# Jumbo_Programmer.net
KiCad netlist of a schematic drawn in EAGLE
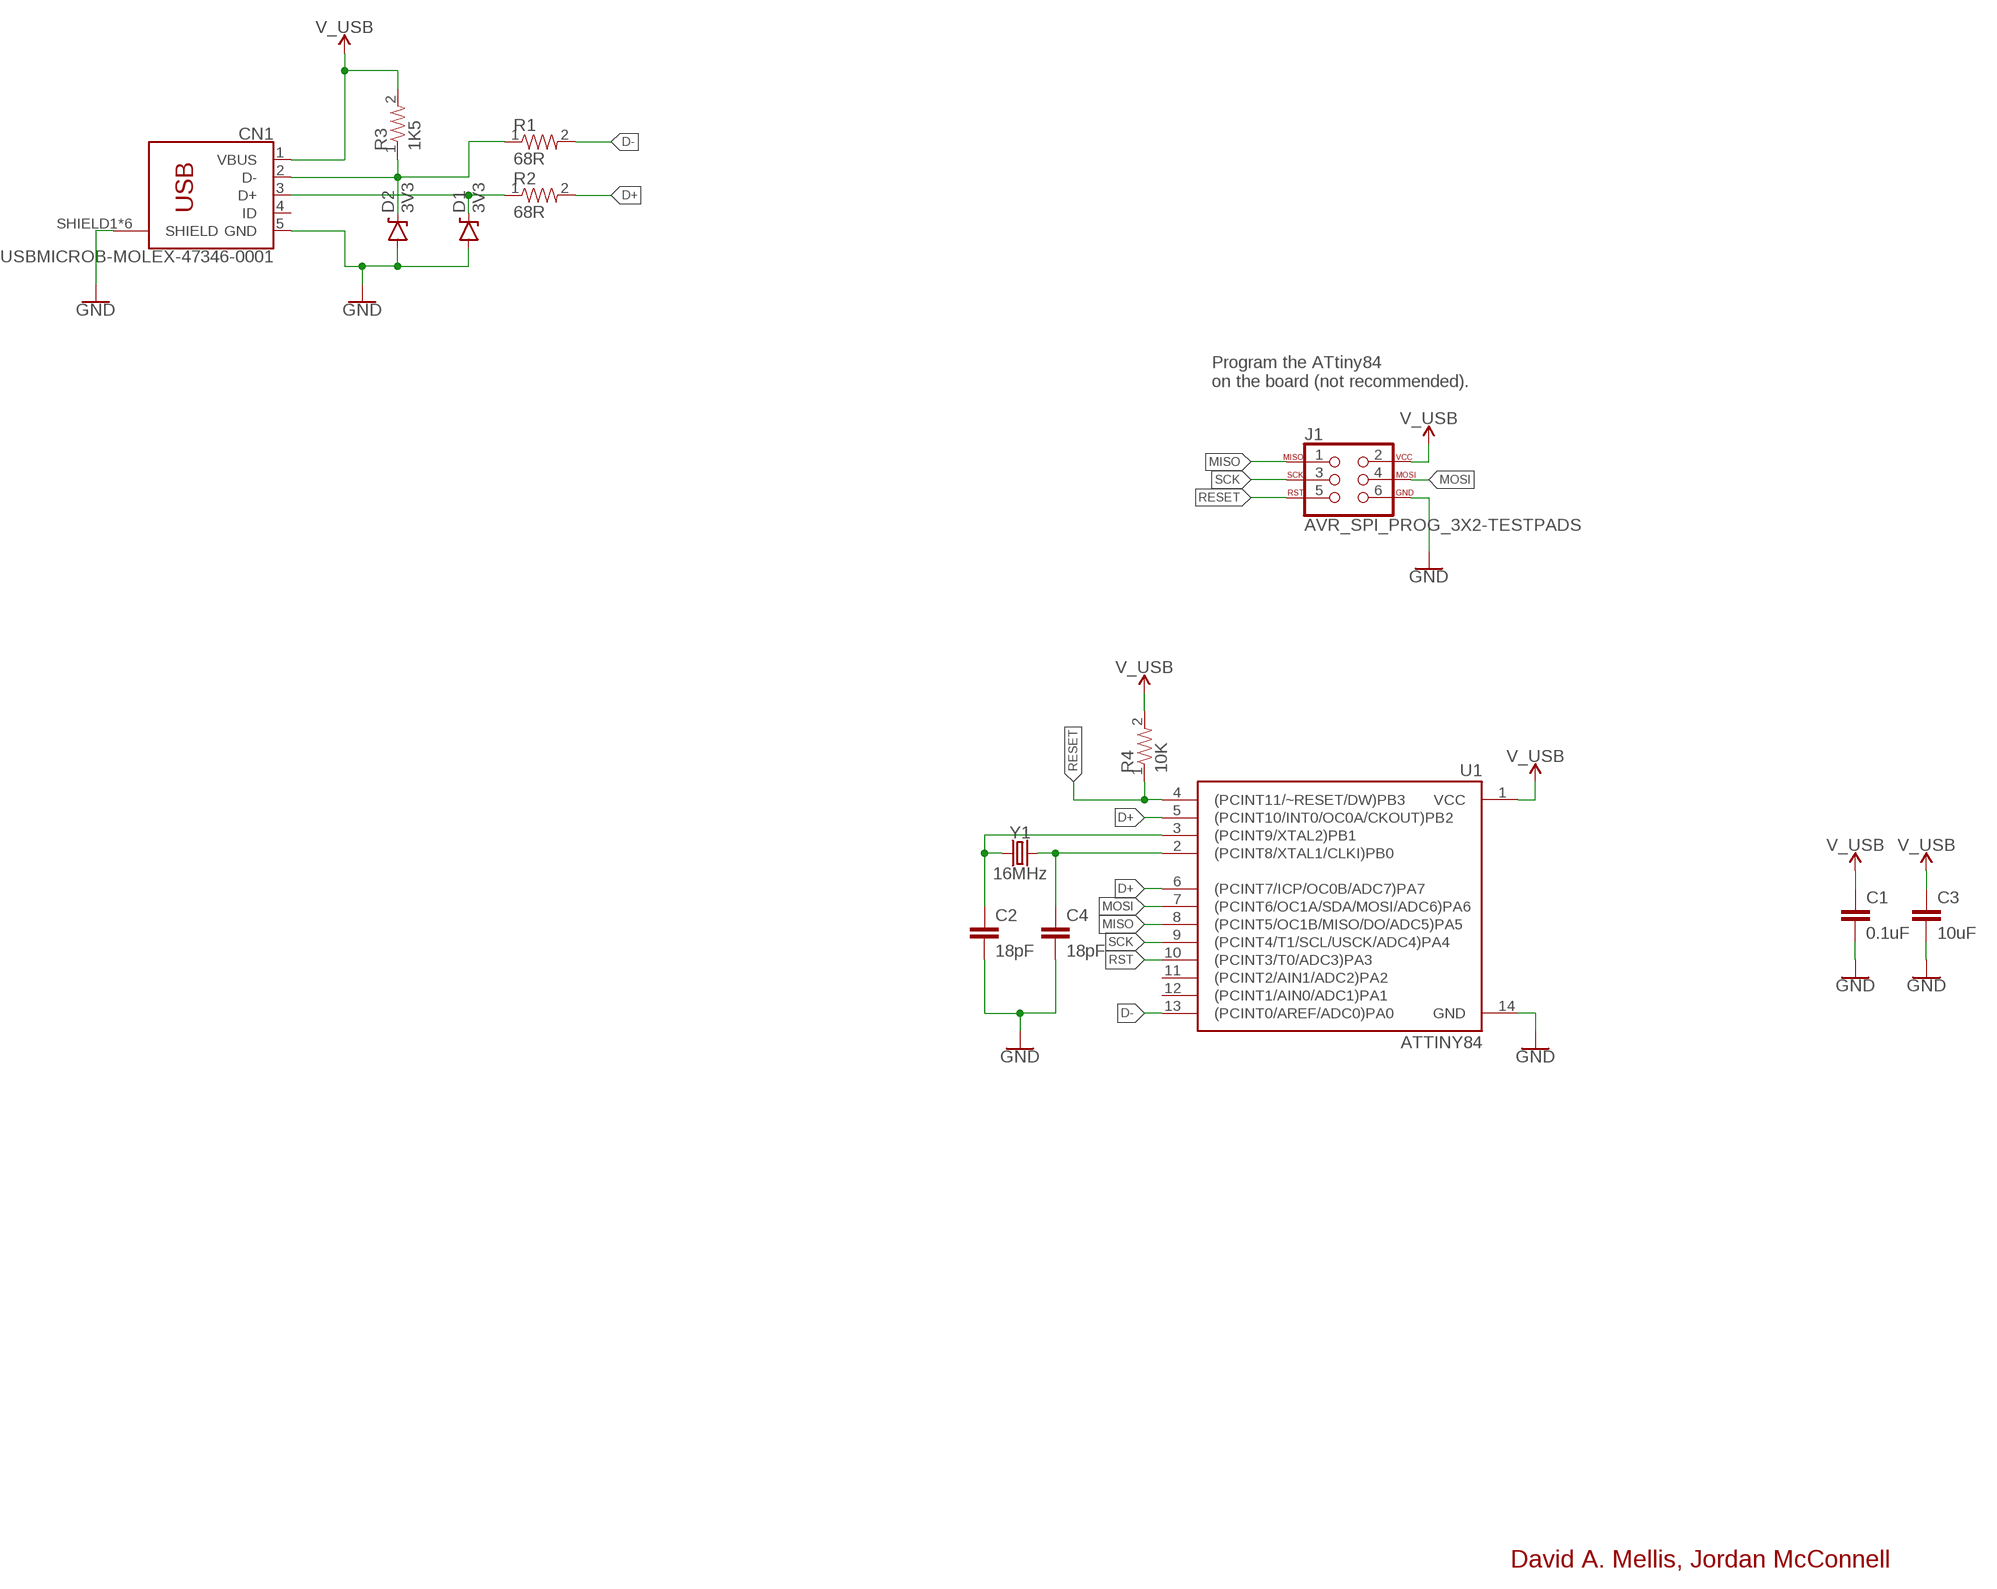
[diagram p0: schematic, sheet 1, part 1 of 2]
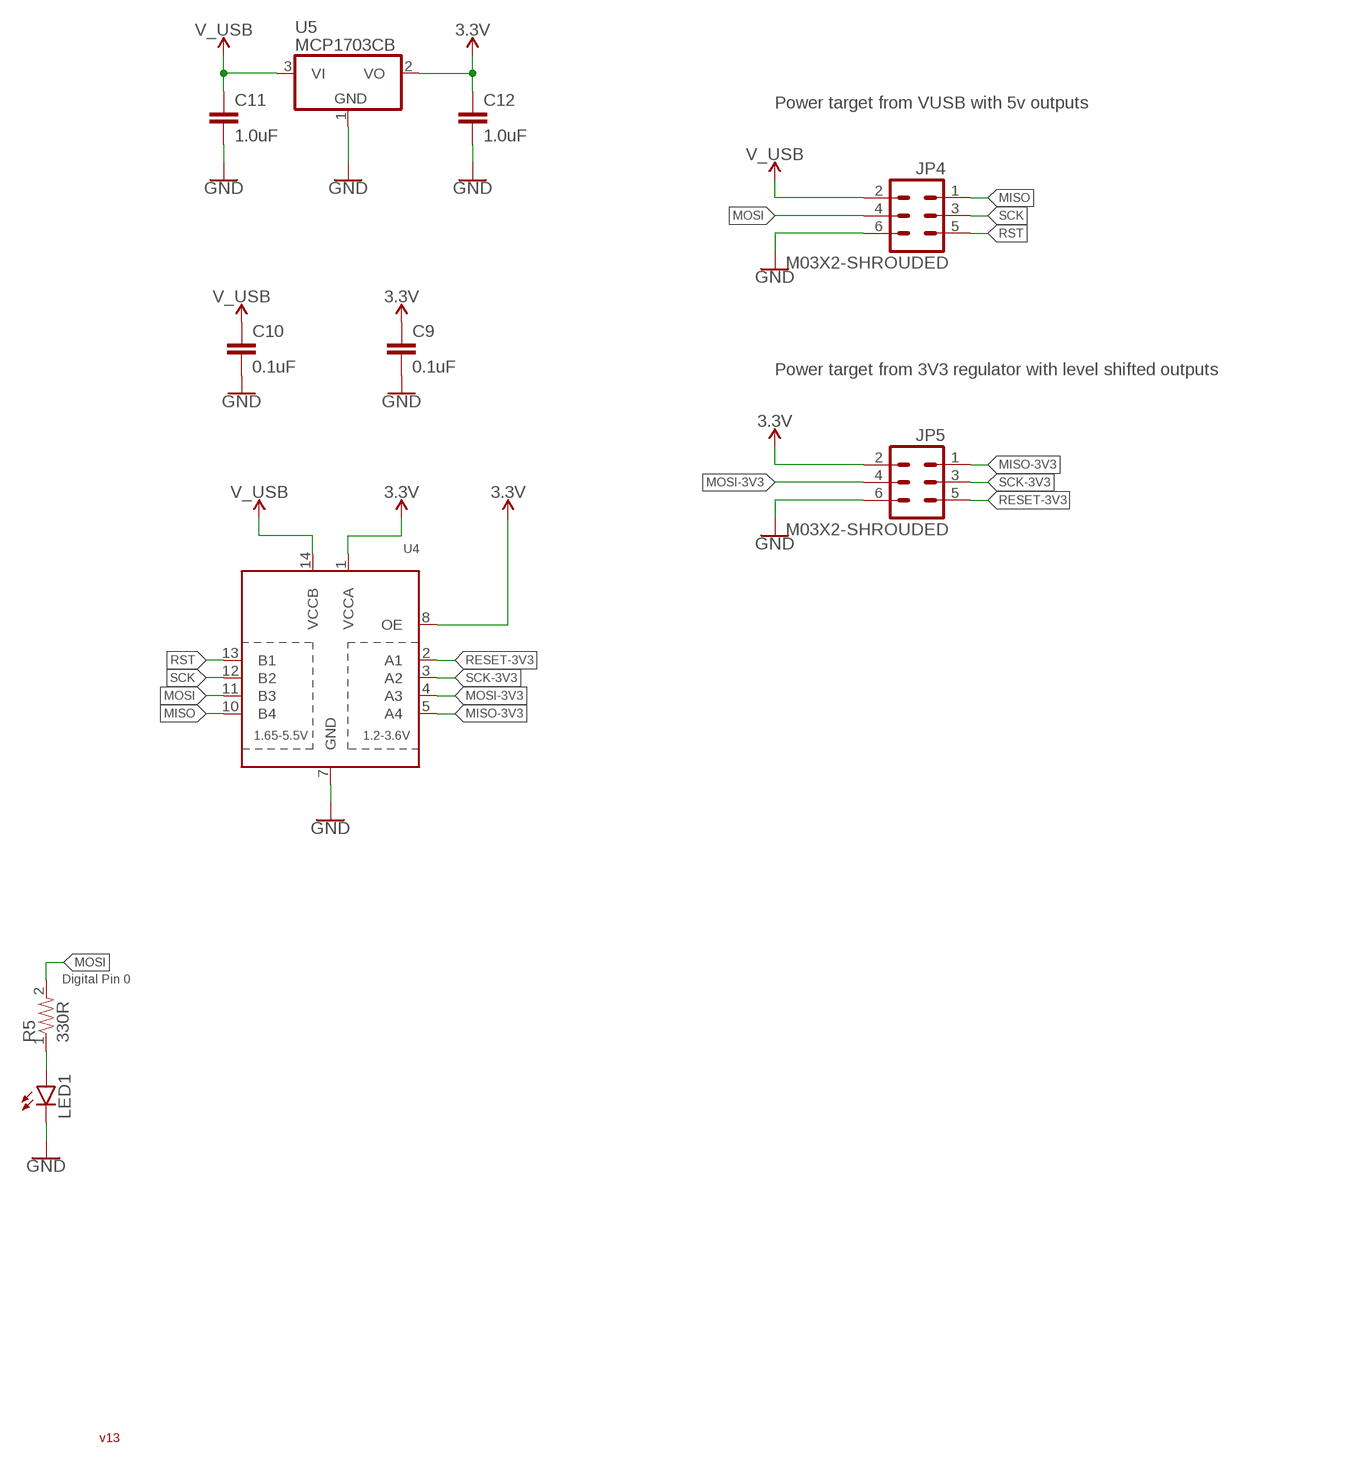
[diagram p1: schematic, sheet 1, part 2 of 2]

(export (version "E")
  (design (tool "Eeschema 10.0.6"))
  (components
    (comp (ref "C1")
      (value "0.1uF")
      (footprint "eagle-import:0603-CAP")
      (libsource (lib "eagle-import") (part "CAPACITOR-0603"))
    )
    (comp (ref "C2")
      (value "18pF")
      (footprint "eagle-import:0603-CAP")
      (libsource (lib "eagle-import") (part "CAPACITOR-0603"))
    )
    (comp (ref "C3")
      (value "10uF")
      (footprint "eagle-import:0603-CAP")
      (libsource (lib "eagle-import") (part "CAPACITOR-0603"))
    )
    (comp (ref "C4")
      (value "18pF")
      (footprint "eagle-import:0603-CAP")
      (libsource (lib "eagle-import") (part "CAPACITOR-0603"))
    )
    (comp (ref "C9")
      (value "0.1uF")
      (footprint "eagle-import:0603-CAP")
      (libsource (lib "eagle-import") (part "CAPACITOR-0603"))
    )
    (comp (ref "C10")
      (value "0.1uF")
      (footprint "eagle-import:0603-CAP")
      (libsource (lib "eagle-import") (part "CAPACITOR-0603"))
    )
    (comp (ref "C11")
      (value "1.0uF")
      (footprint "eagle-import:0603-CAP")
      (libsource (lib "eagle-import") (part "CAPACITOR-0603"))
    )
    (comp (ref "C12")
      (value "1.0uF")
      (footprint "eagle-import:0603-CAP")
      (libsource (lib "eagle-import") (part "CAPACITOR-0603"))
    )
    (comp (ref "CN1")
      (value "USBMICROB-MOLEX-47346-0001")
      (footprint "eagle-import:MOLEX_47346-0001")
      (libsource (lib "eagle-import") (part "USBMICROB-MOLEX-47346-0001"))
    )
    (comp (ref "D1")
      (value "3V3")
      (footprint "eagle-import:SOD-323")
      (libsource (lib "eagle-import") (part "DIODE-ZENER-SOD-323"))
    )
    (comp (ref "D2")
      (value "3V3")
      (footprint "eagle-import:SOD-323")
      (libsource (lib "eagle-import") (part "DIODE-ZENER-SOD-323"))
    )
    (comp (ref "J1")
      (value "AVR_SPI_PROG_3X2-TESTPADS")
      (footprint "eagle-import:2X3_TEST_PADS")
      (libsource (lib "eagle-import") (part "AVR_SPI_PROG_3X2-TESTPADS"))
    )
    (comp (ref "JP4")
      (value "M03X2-SHROUDED")
      (footprint "eagle-import:2X3-SHROUDED-B")
      (libsource (lib "eagle-import") (part "M03X2-SHROUDED"))
    )
    (comp (ref "JP5")
      (value "M03X2-SHROUDED")
      (footprint "eagle-import:2X3-SHROUDED-B")
      (libsource (lib "eagle-import") (part "M03X2-SHROUDED"))
    )
    (comp (ref "LED1")
      (value "LED0603")
      (footprint "eagle-import:LED-0603")
      (libsource (lib "eagle-import") (part "LED0603"))
    )
    (comp (ref "R1")
      (value "68R")
      (footprint "eagle-import:0603-RES")
      (libsource (lib "eagle-import") (part "RESISTOR-0603"))
    )
    (comp (ref "R2")
      (value "68R")
      (footprint "eagle-import:0603-RES")
      (libsource (lib "eagle-import") (part "RESISTOR-0603"))
    )
    (comp (ref "R3")
      (value "1K5")
      (footprint "eagle-import:0603-RES")
      (libsource (lib "eagle-import") (part "RESISTOR-0603"))
    )
    (comp (ref "R4")
      (value "10K")
      (footprint "eagle-import:0603-RES")
      (libsource (lib "eagle-import") (part "RESISTOR-0603"))
    )
    (comp (ref "R5")
      (value "330R")
      (footprint "eagle-import:0603-RES")
      (libsource (lib "eagle-import") (part "RESISTOR-0603"))
    )
    (comp (ref "U1")
      (value "ATTINY84")
      (footprint "eagle-import:SO14")
      (libsource (lib "eagle-import") (part "ATTINY84"))
    )
    (comp (ref "U4")
      (value "TXB0104PWR")
      (footprint "eagle-import:TSSOP14")
      (libsource (lib "eagle-import") (part "TXB0104PWR"))
    )
    (comp (ref "U5")
      (value "MCP1703CB")
      (footprint "eagle-import:SOT23")
      (libsource (lib "eagle-import") (part "MCP1703CB"))
    )
    (comp (ref "Y1")
      (value "16MHz")
      (footprint "eagle-import:CRYSTAL-SMD-5X3.2-4PAD")
      (libsource (lib "eagle-import") (part "CRYSTAL-16MHZSMD-5X3.2"))
    )
  )
  (nets
    (net (code "1") (name "3.3V") (class "Default")
      (node (ref "C12") (pin "1") (pinfunction "1_1") (pintype "passive"))
      (node (ref "C9") (pin "1") (pinfunction "1_1") (pintype "passive"))
      (node (ref "JP5") (pin "2") (pinfunction "2_2") (pintype "passive"))
      (node (ref "U4") (pin "1") (pinfunction "VCCA_1") (pintype "bidirectional"))
      (node (ref "U4") (pin "8") (pinfunction "OE_8") (pintype "bidirectional"))
      (node (ref "U5") (pin "2") (pinfunction "VO_2") (pintype "passive"))
    )
    (net (code "2") (name "D+") (class "Default")
      (node (ref "R2") (pin "2") (pinfunction "2_2") (pintype "passive"))
      (node (ref "U1") (pin "5") (pinfunction "(PCINT10/INT0/OC0A/CKOUT)PB2_5") (pintype "bidirectional"))
      (node (ref "U1") (pin "6") (pinfunction "(PCINT7/ICP/OC0B/ADC7)PA7_6") (pintype "bidirectional"))
    )
    (net (code "3") (name "D-") (class "Default")
      (node (ref "R1") (pin "2") (pinfunction "2_2") (pintype "passive"))
      (node (ref "U1") (pin "13") (pinfunction "(PCINT0/AREF/ADC0)PA0_13") (pintype "bidirectional"))
    )
    (net (code "4") (name "GND") (class "Default")
      (node (ref "C1") (pin "2") (pinfunction "2_2") (pintype "passive"))
      (node (ref "C10") (pin "2") (pinfunction "2_2") (pintype "passive"))
      (node (ref "C11") (pin "2") (pinfunction "2_2") (pintype "passive"))
      (node (ref "C12") (pin "2") (pinfunction "2_2") (pintype "passive"))
      (node (ref "C2") (pin "2") (pinfunction "2_2") (pintype "passive"))
      (node (ref "C3") (pin "2") (pinfunction "2_2") (pintype "passive"))
      (node (ref "C4") (pin "2") (pinfunction "2_2") (pintype "passive"))
      (node (ref "C9") (pin "2") (pinfunction "2_2") (pintype "passive"))
      (node (ref "CN1") (pin "5") (pinfunction "GND_5") (pintype "power_in"))
      (node (ref "CN1") (pin "SHIELD1") (pinfunction "SHIELD_SHIELD1") (pintype "bidirectional"))
      (node (ref "CN1") (pin "SHIELD2") (pinfunction "SHIELD_SHIELD2") (pintype "bidirectional"))
      (node (ref "CN1") (pin "SHIELD3") (pinfunction "SHIELD_SHIELD3") (pintype "bidirectional"))
      (node (ref "CN1") (pin "SHIELD4") (pinfunction "SHIELD_SHIELD4") (pintype "bidirectional"))
      (node (ref "CN1") (pin "SHIELD5") (pinfunction "SHIELD_SHIELD5") (pintype "bidirectional"))
      (node (ref "CN1") (pin "SHIELD6") (pinfunction "SHIELD_SHIELD6") (pintype "bidirectional"))
      (node (ref "D1") (pin "A") (pinfunction "A_A") (pintype "passive"))
      (node (ref "D2") (pin "A") (pinfunction "A_A") (pintype "passive"))
      (node (ref "J1") (pin "6") (pinfunction "6_6") (pintype "passive"))
      (node (ref "JP4") (pin "6") (pinfunction "6_6") (pintype "passive"))
      (node (ref "JP5") (pin "6") (pinfunction "6_6") (pintype "passive"))
      (node (ref "LED1") (pin "C") (pinfunction "C_C") (pintype "passive"))
      (node (ref "U1") (pin "14") (pinfunction "GND_14") (pintype "bidirectional"))
      (node (ref "U4") (pin "7") (pinfunction "GND_7") (pintype "bidirectional"))
      (node (ref "U5") (pin "1") (pinfunction "GND_1") (pintype "passive"))
    )
    (net (code "5") (name "MISO") (class "Default")
      (node (ref "J1") (pin "1") (pinfunction "1_1") (pintype "passive"))
      (node (ref "JP4") (pin "1") (pinfunction "1_1") (pintype "passive"))
      (node (ref "U1") (pin "8") (pinfunction "(PCINT5/OC1B/MISO/DO/ADC5)PA5_8") (pintype "bidirectional"))
      (node (ref "U4") (pin "10") (pinfunction "B4_10") (pintype "bidirectional"))
    )
    (net (code "6") (name "MISO-3V3") (class "Default")
      (node (ref "JP5") (pin "1") (pinfunction "1_1") (pintype "passive"))
      (node (ref "U4") (pin "5") (pinfunction "A4_5") (pintype "bidirectional"))
    )
    (net (code "7") (name "MOSI") (class "Default")
      (node (ref "J1") (pin "4") (pinfunction "4_4") (pintype "passive"))
      (node (ref "JP4") (pin "4") (pinfunction "4_4") (pintype "passive"))
      (node (ref "R5") (pin "2") (pinfunction "2_2") (pintype "passive"))
      (node (ref "U1") (pin "7") (pinfunction "(PCINT6/OC1A/SDA/MOSI/ADC6)PA6_7") (pintype "bidirectional"))
      (node (ref "U4") (pin "11") (pinfunction "B3_11") (pintype "bidirectional"))
    )
    (net (code "8") (name "MOSI-3V3") (class "Default")
      (node (ref "JP5") (pin "4") (pinfunction "4_4") (pintype "passive"))
      (node (ref "U4") (pin "4") (pinfunction "A3_4") (pintype "bidirectional"))
    )
    (net (code "9") (name "Net-(CN1-D+)") (class "Default")
      (node (ref "CN1") (pin "3") (pinfunction "D+_3") (pintype "bidirectional"))
      (node (ref "D1") (pin "C") (pinfunction "C_C") (pintype "passive"))
      (node (ref "R2") (pin "1") (pinfunction "1_1") (pintype "passive"))
    )
    (net (code "10") (name "Net-(CN1-D-)") (class "Default")
      (node (ref "CN1") (pin "2") (pinfunction "D-_2") (pintype "bidirectional"))
      (node (ref "D2") (pin "C") (pinfunction "C_C") (pintype "passive"))
      (node (ref "R1") (pin "1") (pinfunction "1_1") (pintype "passive"))
      (node (ref "R3") (pin "1") (pinfunction "1_1") (pintype "passive"))
    )
    (net (code "11") (name "Net-(LED1-PadA)") (class "Default")
      (node (ref "LED1") (pin "A") (pinfunction "A_A") (pintype "passive"))
      (node (ref "R5") (pin "1") (pinfunction "1_1") (pintype "passive"))
    )
    (net (code "12") (name "Net-(U1-(PCINT8{slash}XTAL1{slash}CLKI)PB0)") (class "Default")
      (node (ref "C4") (pin "1") (pinfunction "1_1") (pintype "passive"))
      (node (ref "U1") (pin "2") (pinfunction "(PCINT8/XTAL1/CLKI)PB0_2") (pintype "bidirectional"))
      (node (ref "Y1") (pin "3") (pinfunction "2_3") (pintype "passive"))
    )
    (net (code "13") (name "Net-(U1-(PCINT9{slash}XTAL2)PB1)") (class "Default")
      (node (ref "C2") (pin "1") (pinfunction "1_1") (pintype "passive"))
      (node (ref "U1") (pin "3") (pinfunction "(PCINT9/XTAL2)PB1_3") (pintype "bidirectional"))
      (node (ref "Y1") (pin "1") (pinfunction "1_1") (pintype "passive"))
    )
    (net (code "14") (name "RESET") (class "Default")
      (node (ref "J1") (pin "5") (pinfunction "5_5") (pintype "passive"))
      (node (ref "R4") (pin "1") (pinfunction "1_1") (pintype "passive"))
      (node (ref "U1") (pin "4") (pinfunction "(PCINT11/~{RESET/DW})PB3_4") (pintype "bidirectional"))
    )
    (net (code "15") (name "RESET-3V3") (class "Default")
      (node (ref "JP5") (pin "5") (pinfunction "5_5") (pintype "passive"))
      (node (ref "U4") (pin "2") (pinfunction "A1_2") (pintype "bidirectional"))
    )
    (net (code "16") (name "RST") (class "Default")
      (node (ref "JP4") (pin "5") (pinfunction "5_5") (pintype "passive"))
      (node (ref "U1") (pin "10") (pinfunction "(PCINT3/T0/ADC3)PA3_10") (pintype "bidirectional"))
      (node (ref "U4") (pin "13") (pinfunction "B1_13") (pintype "bidirectional"))
    )
    (net (code "17") (name "SCK") (class "Default")
      (node (ref "J1") (pin "3") (pinfunction "3_3") (pintype "passive"))
      (node (ref "JP4") (pin "3") (pinfunction "3_3") (pintype "passive"))
      (node (ref "U1") (pin "9") (pinfunction "(PCINT4/T1/SCL/USCK/ADC4)PA4_9") (pintype "bidirectional"))
      (node (ref "U4") (pin "12") (pinfunction "B2_12") (pintype "bidirectional"))
    )
    (net (code "18") (name "SCK-3V3") (class "Default")
      (node (ref "JP5") (pin "3") (pinfunction "3_3") (pintype "passive"))
      (node (ref "U4") (pin "3") (pinfunction "A2_3") (pintype "bidirectional"))
    )
    (net (code "19") (name "V_USB") (class "Default")
      (node (ref "C1") (pin "1") (pinfunction "1_1") (pintype "passive"))
      (node (ref "C10") (pin "1") (pinfunction "1_1") (pintype "passive"))
      (node (ref "C11") (pin "1") (pinfunction "1_1") (pintype "passive"))
      (node (ref "C3") (pin "1") (pinfunction "1_1") (pintype "passive"))
      (node (ref "CN1") (pin "1") (pinfunction "VBUS_1") (pintype "power_in"))
      (node (ref "J1") (pin "2") (pinfunction "2_2") (pintype "passive"))
      (node (ref "JP4") (pin "2") (pinfunction "2_2") (pintype "passive"))
      (node (ref "R3") (pin "2") (pinfunction "2_2") (pintype "passive"))
      (node (ref "R4") (pin "2") (pinfunction "2_2") (pintype "passive"))
      (node (ref "U1") (pin "1") (pinfunction "VCC_1") (pintype "bidirectional"))
      (node (ref "U4") (pin "14") (pinfunction "VCCB_14") (pintype "bidirectional"))
      (node (ref "U5") (pin "3") (pinfunction "VI_3") (pintype "input"))
    )
    (net (code "20") (name "unconnected-(CN1-ID-Pad4)") (class "Default")
      (node (ref "CN1") (pin "4") (pinfunction "ID_4") (pintype "bidirectional"))
    )
    (net (code "21") (name "unconnected-(U1-(PCINT1{slash}AIN0{slash}ADC1)PA1-Pad12)") (class "Default")
      (node (ref "U1") (pin "12") (pinfunction "(PCINT1/AIN0/ADC1)PA1_12") (pintype "bidirectional"))
    )
    (net (code "22") (name "unconnected-(U1-(PCINT2{slash}AIN1{slash}ADC2)PA2-Pad11)") (class "Default")
      (node (ref "U1") (pin "11") (pinfunction "(PCINT2/AIN1/ADC2)PA2_11") (pintype "bidirectional"))
    )
  )
)
